# maus-blenano2-mk-1_0_2.net
KiCad netlist of a schematic drawn in EAGLE
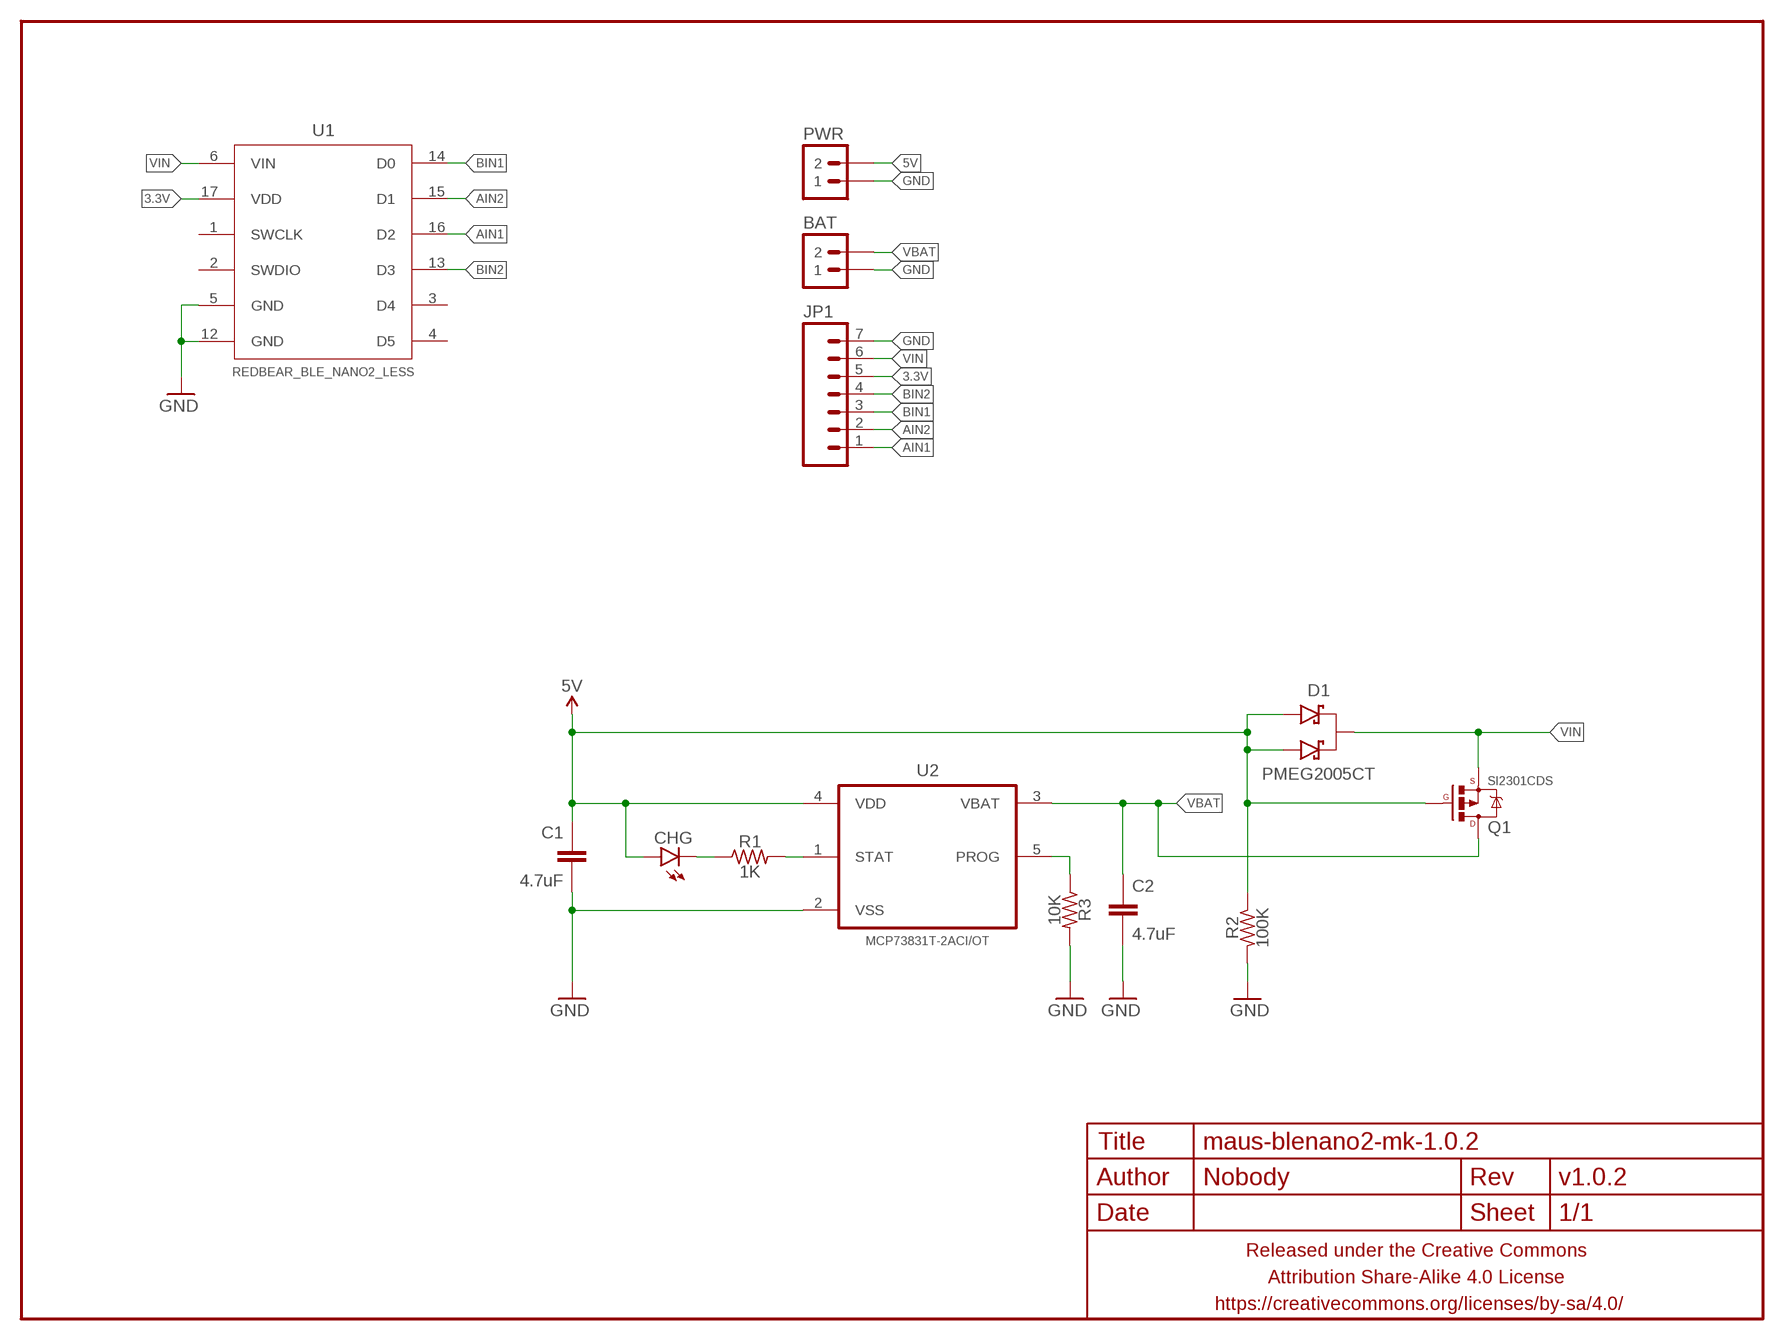
[diagram p0: schematic, sheet 1]

(export (version "E")
  (design (tool "Eeschema 10.0.6"))
  (components
    (comp (ref "BAT")
      (value "M02JST-SH-RA")
      (footprint "eagle-import:JST-2-SH-RA")
      (libsource (lib "eagle-import") (part "M02JST-SH-RA"))
    )
    (comp (ref "C1")
      (value "4.7uF")
      (footprint "eagle-import:C0603-TIGHTER")
      (libsource (lib "eagle-import") (part "CAPACITOR-CERAMICC0603-TIGHTER"))
    )
    (comp (ref "C2")
      (value "4.7uF")
      (footprint "eagle-import:C0603-TIGHTER")
      (libsource (lib "eagle-import") (part "CAPACITOR-CERAMICC0603-TIGHTER"))
    )
    (comp (ref "CHG")
      (value "LED0603-TIGHT")
      (footprint "eagle-import:LED-0603-TIGHT")
      (libsource (lib "eagle-import") (part "LED0603-TIGHT"))
    )
    (comp (ref "D1")
      (value "PMEG2005CT")
      (footprint "eagle-import:SOT23")
      (libsource (lib "eagle-import") (part "DIODE-SCHOTTKY-DUALPMEG2005CT"))
    )
    (comp (ref "FRAME1")
      (value "FRAME-LETTERNO_PACKAGE")
      (footprint "eagle-import:DUMMY")
      (fields (field (name "VERSION") "v1.0.2") (field (name "DESIGNER") "Nobody"))
      (libsource (lib "eagle-import") (part "FRAME-LETTERNO_PACKAGE"))
    )
    (comp (ref "JP1")
      (value "M07PTH-CENTERED")
      (footprint "eagle-import:1X07_CENTERED")
      (libsource (lib "eagle-import") (part "M07PTH-CENTERED"))
    )
    (comp (ref "PWR")
      (value "M02JST-SH-RA")
      (footprint "eagle-import:JST-2-SH-RA")
      (libsource (lib "eagle-import") (part "M02JST-SH-RA"))
    )
    (comp (ref "Q1")
      (value "SI2301CDS")
      (footprint "eagle-import:SOT23")
      (libsource (lib "eagle-import") (part "MOSFET-PCHANNELSOT-23"))
    )
    (comp (ref "R1")
      (value "1K")
      (footprint "eagle-import:R0603-TIGHTER")
      (libsource (lib "eagle-import") (part "RESISTORR0603-TIGHTER"))
    )
    (comp (ref "R2")
      (value "100K")
      (footprint "eagle-import:R0603-TIGHTER")
      (libsource (lib "eagle-import") (part "RESISTORR0603-TIGHTER"))
    )
    (comp (ref "R3")
      (value "10K")
      (footprint "eagle-import:R0603-TIGHTER")
      (libsource (lib "eagle-import") (part "RESISTORR0603-TIGHTER"))
    )
    (comp (ref "U1")
      (value "REDBEAR_BLE_NANO2_LESS")
      (footprint "eagle-import:REDBEAR_BLE_NANO2_LESS")
      (libsource (lib "eagle-import") (part "REDBEAR_BLE_NANO2_LESS"))
    )
    (comp (ref "U2")
      (value "MCP73831T-2ACI/OT")
      (footprint "eagle-import:SOT95P280X145-5N")
      (libsource (lib "eagle-import") (part "MCP73831T-2ACI/OT"))
    )
  )
  (nets
    (net (code "1") (name "3.3V") (class "Default")
      (node (ref "JP1") (pin "5") (pinfunction "5_5") (pintype "passive"))
      (node (ref "U1") (pin "17") (pinfunction "VDD_17") (pintype "bidirectional"))
    )
    (net (code "2") (name "5V") (class "Default")
      (node (ref "C1") (pin "1") (pinfunction "1_1") (pintype "passive"))
      (node (ref "CHG") (pin "A") (pinfunction "A_A") (pintype "passive"))
      (node (ref "D1") (pin "1") (pinfunction "A1_1") (pintype "passive"))
      (node (ref "D1") (pin "2") (pinfunction "A2_2") (pintype "passive"))
      (node (ref "PWR") (pin "2") (pinfunction "2_2") (pintype "passive"))
      (node (ref "Q1") (pin "1") (pinfunction "G_1") (pintype "passive"))
      (node (ref "R2") (pin "1") (pinfunction "1_1") (pintype "passive"))
      (node (ref "U2") (pin "4") (pinfunction "VDD_4") (pintype "power_in"))
    )
    (net (code "3") (name "AIN1") (class "Default")
      (node (ref "JP1") (pin "1") (pinfunction "1_1") (pintype "passive"))
      (node (ref "U1") (pin "16") (pinfunction "D2_16") (pintype "bidirectional"))
    )
    (net (code "4") (name "AIN2") (class "Default")
      (node (ref "JP1") (pin "2") (pinfunction "2_2") (pintype "passive"))
      (node (ref "U1") (pin "15") (pinfunction "D1_15") (pintype "bidirectional"))
    )
    (net (code "5") (name "BIN1") (class "Default")
      (node (ref "JP1") (pin "3") (pinfunction "3_3") (pintype "passive"))
      (node (ref "U1") (pin "14") (pinfunction "D0_14") (pintype "bidirectional"))
    )
    (net (code "6") (name "BIN2") (class "Default")
      (node (ref "JP1") (pin "4") (pinfunction "4_4") (pintype "passive"))
      (node (ref "U1") (pin "13") (pinfunction "D3_13") (pintype "bidirectional"))
    )
    (net (code "7") (name "GND") (class "Default")
      (node (ref "BAT") (pin "1") (pinfunction "1_1") (pintype "passive"))
      (node (ref "C1") (pin "2") (pinfunction "2_2") (pintype "passive"))
      (node (ref "C2") (pin "2") (pinfunction "2_2") (pintype "passive"))
      (node (ref "JP1") (pin "7") (pinfunction "7_7") (pintype "passive"))
      (node (ref "PWR") (pin "1") (pinfunction "1_1") (pintype "passive"))
      (node (ref "R2") (pin "2") (pinfunction "2_2") (pintype "passive"))
      (node (ref "R3") (pin "2") (pinfunction "2_2") (pintype "passive"))
      (node (ref "U1") (pin "12") (pinfunction "GND_12") (pintype "bidirectional"))
      (node (ref "U1") (pin "5") (pinfunction "GND_5") (pintype "bidirectional"))
      (node (ref "U2") (pin "2") (pinfunction "VSS_2") (pintype "power_in"))
    )
    (net (code "8") (name "Net-(CHG-PadC)") (class "Default")
      (node (ref "CHG") (pin "C") (pinfunction "C_C") (pintype "passive"))
      (node (ref "R1") (pin "1") (pinfunction "1_1") (pintype "passive"))
    )
    (net (code "9") (name "Net-(U2-PROG)") (class "Default")
      (node (ref "R3") (pin "1") (pinfunction "1_1") (pintype "passive"))
      (node (ref "U2") (pin "5") (pinfunction "PROG_5") (pintype "input"))
    )
    (net (code "10") (name "Net-(U2-STAT)") (class "Default")
      (node (ref "R1") (pin "2") (pinfunction "2_2") (pintype "passive"))
      (node (ref "U2") (pin "1") (pinfunction "STAT_1") (pintype "output"))
    )
    (net (code "11") (name "VBAT") (class "Default")
      (node (ref "BAT") (pin "2") (pinfunction "2_2") (pintype "passive"))
      (node (ref "C2") (pin "1") (pinfunction "1_1") (pintype "passive"))
      (node (ref "Q1") (pin "3") (pinfunction "D_3") (pintype "passive"))
      (node (ref "U2") (pin "3") (pinfunction "VBAT_3") (pintype "output"))
    )
    (net (code "12") (name "VIN") (class "Default")
      (node (ref "D1") (pin "3") (pinfunction "K_3") (pintype "passive"))
      (node (ref "JP1") (pin "6") (pinfunction "6_6") (pintype "passive"))
      (node (ref "Q1") (pin "2") (pinfunction "S_2") (pintype "passive"))
      (node (ref "U1") (pin "6") (pinfunction "VIN_6") (pintype "bidirectional"))
    )
    (net (code "13") (name "unconnected-(U1-D4-Pad3)") (class "Default")
      (node (ref "U1") (pin "3") (pinfunction "D4_3") (pintype "bidirectional"))
    )
    (net (code "14") (name "unconnected-(U1-D5-Pad4)") (class "Default")
      (node (ref "U1") (pin "4") (pinfunction "D5_4") (pintype "bidirectional"))
    )
    (net (code "15") (name "unconnected-(U1-SWCLK-Pad1)") (class "Default")
      (node (ref "U1") (pin "1") (pinfunction "SWCLK_1") (pintype "bidirectional"))
    )
    (net (code "16") (name "unconnected-(U1-SWDIO-Pad2)") (class "Default")
      (node (ref "U1") (pin "2") (pinfunction "SWDIO_2") (pintype "bidirectional"))
    )
  )
)
